# BootMemory.net
KiCad netlist of a schematic drawn in Altium Designer
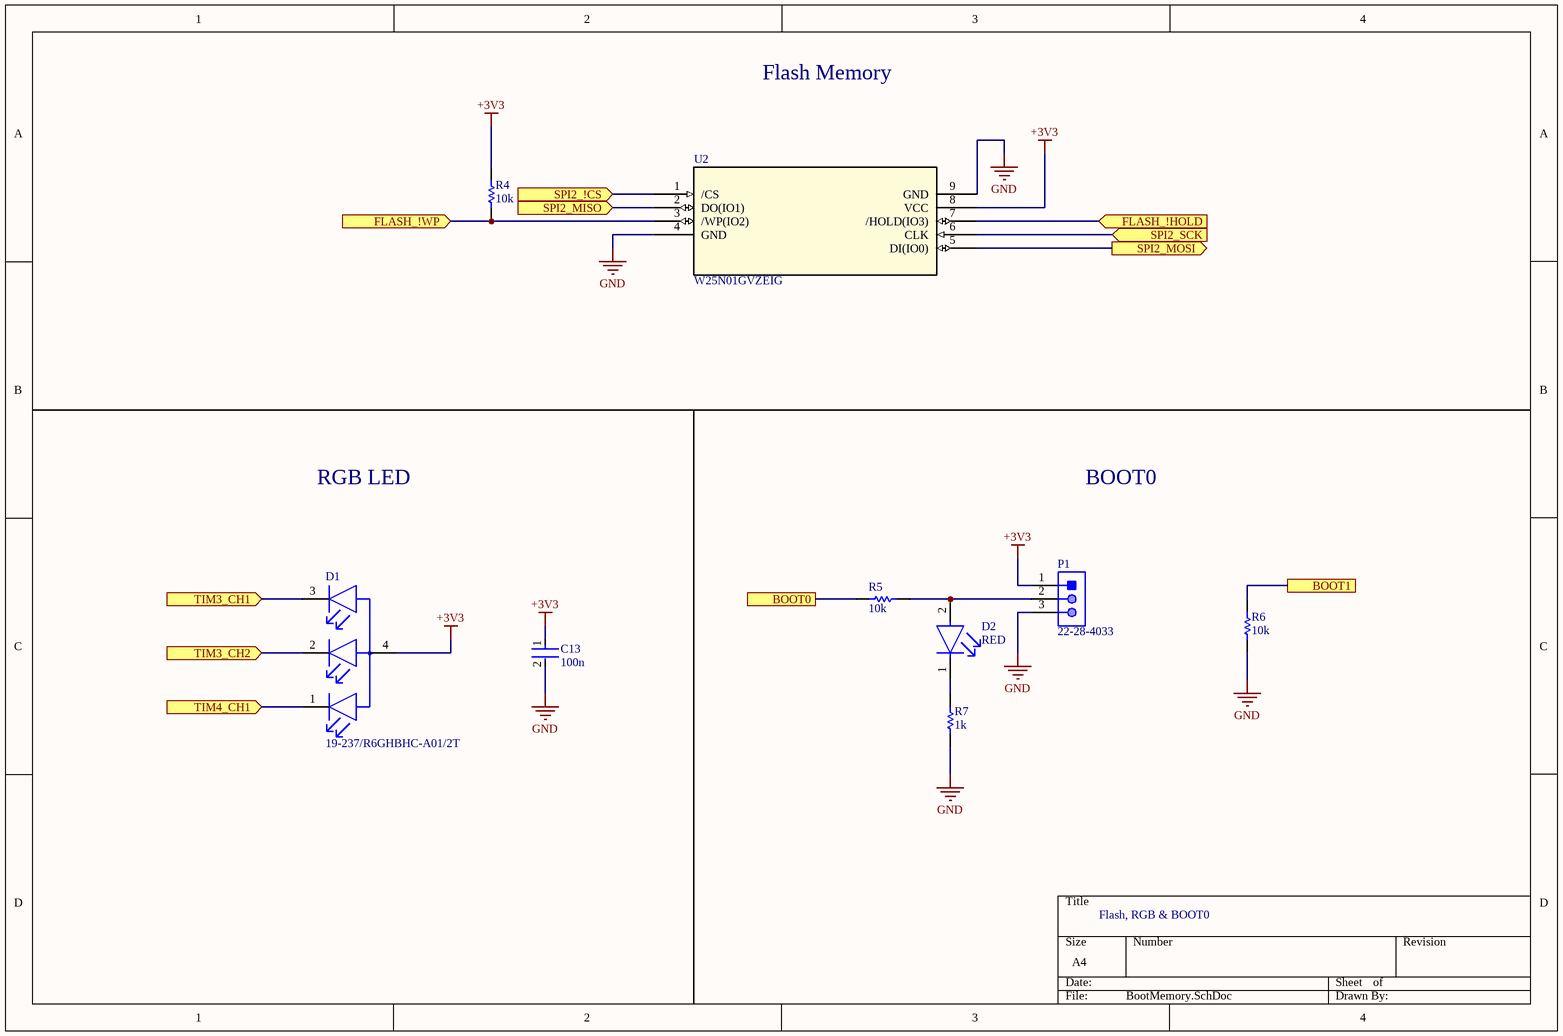
[diagram p0: BootMemory.SchDoc]

(export (version "E")
  (design (tool "Eeschema 10.0.6"))
  (components
    (comp (ref "C13")
      (value "100n")
      (footprint "Capacitor 0402")
      (description "Chip Capacitor 0402")
      (fields (field (name "MANUFACTURER PART NUMBER") "CC0402KRX7R7BB103") (field (name "TOLERANCE") "0.1"))
      (libsource (lib "F4_Flight_Controller") (part "Capacitor 0402"))
    )
    (comp (ref "D1")
      (value "19-237/R6GHBHC-A01/2T")
      (footprint "19337R6GHBHCA012T")
      (description "LED RGB CLEAR CHIP SMD R/A")
      (fields
        (field (name "MANUFACTURER") "Everlight")
        (field (name "OCTOPART") "https://octopart.com/12-23a%2Fr6ghbhc-a01%2F2d-everlight-10561613")
      )
      (libsource (lib "F4_Flight_Controller") (part "LED RGB"))
    )
    (comp (ref "D2")
      (value "RED")
      (footprint "FP-LTST-C190GKT-MFG")
      (description "LED GREEN CLEAR CHIP SMD")
      (fields (field (name "VOLTAGE") "2V"))
      (libsource (lib "Altium Content Vault") (part "8706943c75ba83719d021d2fdc84c58"))
    )
    (comp (ref "P1")
      (value "22-28-4033")
      (footprint "HDRV10W90P254_1X3_1270X483X840P")
      (description "Male Header, Pitch 2.54 mm, 1 x 3 Position, Height 8.38 mm, Tail Length 3.18 mm, RoHS, Bulk")
      (fields (field (name "MANUFACTURER") "Molex"))
      (libsource (lib "F4_Flight_Controller") (part "Male Header 01x03"))
    )
    (comp (ref "R4")
      (value "10k")
      (footprint "Resistor 0402")
      (description "Chip Resistor 0402")
      (fields (field (name "MANUFACTURER") "Vishay") (field (name "PART NUMBER") "CRCW0402120RFKED"))
      (libsource (lib "F4_Flight_Controller") (part "Resistor 0402"))
    )
    (comp (ref "R5")
      (value "10k")
      (footprint "Resistor 0402")
      (description "Chip Resistor 0402")
      (fields (field (name "MANUFACTURER") "Vishay") (field (name "PART NUMBER") "CRCW0402120RFKED"))
      (libsource (lib "F4_Flight_Controller") (part "Resistor 0402"))
    )
    (comp (ref "R6")
      (value "10k")
      (footprint "Resistor 0402")
      (description "Chip Resistor 0402")
      (fields (field (name "MANUFACTURER") "Vishay") (field (name "PART NUMBER") "CRCW0402120RFKED"))
      (libsource (lib "F4_Flight_Controller") (part "Resistor 0402"))
    )
    (comp (ref "R7")
      (value "1k")
      (footprint "Resistor 0402")
      (description "Chip Resistor 0402")
      (fields (field (name "MANUFACTURER") "Vishay") (field (name "PART NUMBER") "CRCW0402120RFKED"))
      (libsource (lib "F4_Flight_Controller") (part "Resistor 0402"))
    )
    (comp (ref "U2")
      (value "W25N01GVZEIG")
      (footprint "SON127P800X600X80-9N-D")
      (description "Flash memory")
      (fields (field (name "COPYRIGHT") "Copyright (C) 2018 Accelerated Designs. All rights reserved"))
      (libsource (lib "F4_Flight_Controller") (part "W25N01GVZEIG"))
    )
  )
  (nets
    (net (code "1") (name "+3V3") (class "Default")
      (node (ref "C13") (pin "1") (pinfunction "1_1") (pintype "passive"))
      (node (ref "D1") (pin "4") (pinfunction "COMMON_ANODE_4") (pintype "passive"))
      (node (ref "P1") (pin "1") (pinfunction "1_1") (pintype "passive"))
      (node (ref "R4") (pin "2") (pinfunction "2_2") (pintype "passive"))
      (node (ref "U2") (pin "8") (pinfunction "VCC_8") (pintype "power_in"))
    )
    (net (code "2") (name "/BOOT0") (class "Default")
      (node (ref "R5") (pin "2") (pinfunction "2_2") (pintype "passive"))
    )
    (net (code "3") (name "/BOOT1") (class "Default")
      (node (ref "R6") (pin "1") (pinfunction "1_1") (pintype "passive"))
    )
    (net (code "4") (name "/FLASH_!HOLD") (class "Default")
      (node (ref "U2") (pin "7") (pinfunction "/HOLD(IO3)_7") (pintype "bidirectional"))
    )
    (net (code "5") (name "/FLASH_!WP") (class "Default")
      (node (ref "R4") (pin "1") (pinfunction "1_1") (pintype "passive"))
      (node (ref "U2") (pin "3") (pinfunction "/WP(IO2)_3") (pintype "bidirectional"))
    )
    (net (code "6") (name "/SPI2_!CS") (class "Default")
      (node (ref "U2") (pin "1") (pinfunction "/CS_1") (pintype "input"))
    )
    (net (code "7") (name "/SPI2_MISO") (class "Default")
      (node (ref "U2") (pin "2") (pinfunction "DO(IO1)_2") (pintype "bidirectional"))
    )
    (net (code "8") (name "/SPI2_MOSI") (class "Default")
      (node (ref "U2") (pin "5") (pinfunction "DI(IO0)_5") (pintype "bidirectional"))
    )
    (net (code "9") (name "/SPI2_SCK") (class "Default")
      (node (ref "U2") (pin "6") (pinfunction "CLK_6") (pintype "input"))
    )
    (net (code "10") (name "/TIM3_CH1") (class "Default")
      (node (ref "D1") (pin "3") (pinfunction "BLUE_C_3") (pintype "passive"))
    )
    (net (code "11") (name "/TIM3_CH2") (class "Default")
      (node (ref "D1") (pin "2") (pinfunction "GREEN_C_2") (pintype "passive"))
    )
    (net (code "12") (name "/TIM4_CH1") (class "Default")
      (node (ref "D1") (pin "1") (pinfunction "RED_C_1") (pintype "passive"))
    )
    (net (code "13") (name "GND") (class "Default")
      (node (ref "C13") (pin "2") (pinfunction "2_2") (pintype "passive"))
      (node (ref "P1") (pin "3") (pinfunction "3_3") (pintype "passive"))
      (node (ref "R6") (pin "2") (pinfunction "2_2") (pintype "passive"))
      (node (ref "R7") (pin "2") (pinfunction "2_2") (pintype "passive"))
      (node (ref "U2") (pin "4") (pinfunction "GND_4") (pintype "passive"))
      (node (ref "U2") (pin "9") (pinfunction "GND_9") (pintype "passive"))
    )
    (net (code "14") (name "Net-(D2-A)") (class "Default")
      (node (ref "D2") (pin "2") (pinfunction "A_2") (pintype "passive"))
      (node (ref "P1") (pin "2") (pinfunction "2_2") (pintype "passive"))
      (node (ref "R5") (pin "1") (pinfunction "1_1") (pintype "passive"))
    )
    (net (code "15") (name "Net-(D2-C)") (class "Default")
      (node (ref "D2") (pin "1") (pinfunction "C_1") (pintype "passive"))
      (node (ref "R7") (pin "1") (pinfunction "1_1") (pintype "passive"))
    )
  )
)
